# TempSensor.net
KiCad netlist of a schematic drawn in Altium Designer
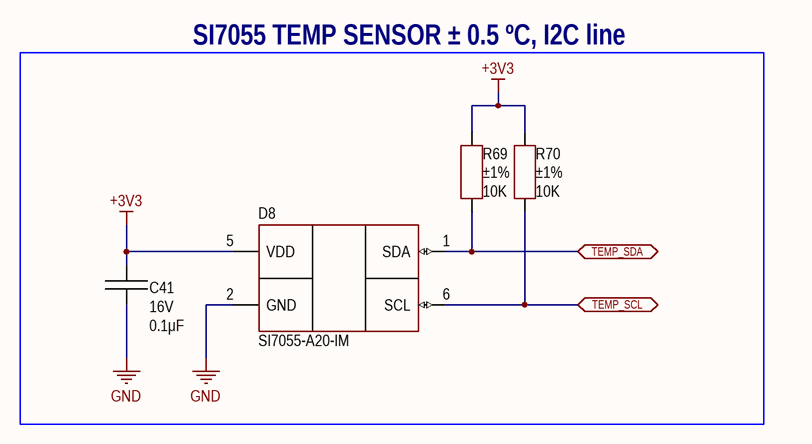
[diagram p0: TempSensor.SchDoc]

(export (version "E")
  (design (tool "Eeschema 10.0.6"))
  (components
    (comp (ref "C41")
      (value "0.1μF")
      (footprint "CAP: 0402")
      (description "±10% 16V Ceramic Capacitor X7R 0402 (1005 Metric)")
      (fields
        (field (name "MANUFACTURER") "Yageo")
        (field (name "PARTNUMBER") "CC0402KRX7R7BB104")
        (field (name "VOLTAGE") "16V")
      )
      (libsource (lib "capacitor") (part "Ceramic_0402"))
    )
    (comp (ref "D8")
      (value "~")
      (footprint "6-WDFN(3x3)")
      (description "Temperature sensor")
      (fields
        (field (name "MANUFACTURER") "Silicon Labs")
        (field (name "VALUEMANUFACTURERPARTNUMBER") "IC temperature sensor, Digital sensor, ±0.5°C, , , -40...+125°C, 6-WDFN")
        (field (name "PARTNUMBER") "SI7055-A20-IM")
      )
      (libsource (lib "MyLib") (part "SI7055-A20-IM"))
    )
    (comp (ref "R69")
      (value "10K")
      (footprint "RES: 0402")
      (description "10 kOhms ±1% 0.063W, 1/16W Chip Resistor 0402 (1005 Metric) Moisture Resistant Thick Film")
      (fields
        (field (name "MANUFACTURER") "Yageo")
        (field (name "PARTNUMBER") "RC0402FR-0710KL")
        (field (name "TOLERANCE") "±1%")
      )
      (libsource (lib "resistor") (part "Resistor_0402"))
    )
    (comp (ref "R70")
      (value "10K")
      (footprint "RES: 0402")
      (description "10 kOhms ±1% 0.063W, 1/16W Chip Resistor 0402 (1005 Metric) Moisture Resistant Thick Film")
      (fields
        (field (name "MANUFACTURER") "Yageo")
        (field (name "PARTNUMBER") "RC0402FR-0710KL")
        (field (name "TOLERANCE") "±1%")
      )
      (libsource (lib "resistor") (part "Resistor_0402"))
    )
  )
  (nets
    (net (code "1") (name "+3V3") (class "Default")
      (node (ref "C41") (pin "2") (pinfunction "2_2") (pintype "passive"))
      (node (ref "D8") (pin "5") (pinfunction "VDD_5") (pintype "power_in"))
      (node (ref "R69") (pin "2") (pinfunction "2_2") (pintype "passive"))
      (node (ref "R70") (pin "2") (pinfunction "2_2") (pintype "passive"))
    )
    (net (code "2") (name "/TEMP_SCL") (class "Default")
      (node (ref "D8") (pin "6") (pinfunction "SCL_6") (pintype "bidirectional"))
      (node (ref "R70") (pin "1") (pinfunction "1_1") (pintype "passive"))
    )
    (net (code "3") (name "/TEMP_SDA") (class "Default")
      (node (ref "D8") (pin "1") (pinfunction "SDA_1") (pintype "bidirectional"))
      (node (ref "R69") (pin "1") (pinfunction "1_1") (pintype "passive"))
    )
    (net (code "4") (name "GND") (class "Default")
      (node (ref "C41") (pin "1") (pinfunction "1_1") (pintype "passive"))
      (node (ref "D8") (pin "2") (pinfunction "GND_2") (pintype "power_in"))
    )
  )
)
